# WiFi_module.net
KiCad netlist of a schematic drawn in Altium Designer
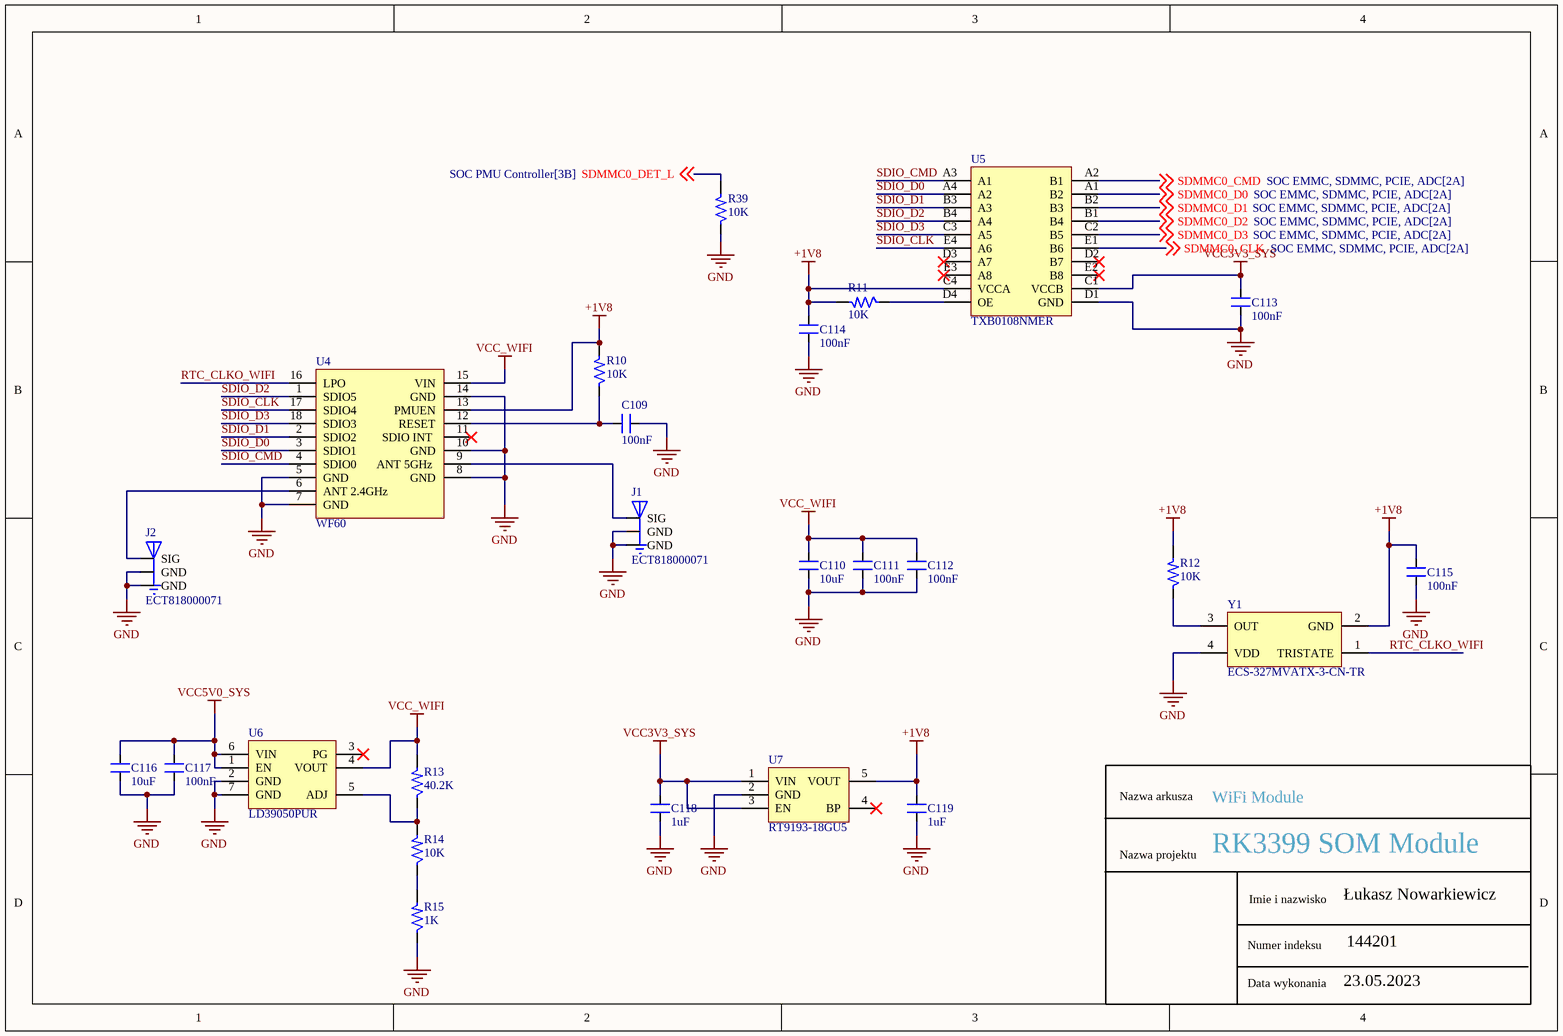
[diagram p0: WiFi module.SchDoc]

(export (version "E")
  (design (tool "Eeschema 10.0.6"))
  (components
    (comp (ref "C109")
      (value "100nF")
      (footprint "CAP_0402")
      (description "0.1µF ±10% 10V Ceramic Capacitor X7R 0402 (1005 Metric)")
      (fields
        (field (name "MANUFACTURER") "Yageo")
        (field (name "MANUFACTURER PART NUMBER") "CC0402KRX7R6BB104")
      )
      (libsource (lib "EsteemPCB_SOM_Course_intlib") (part "CAP_100nF-10V-10%-0402"))
    )
    (comp (ref "C110")
      (value "10uF")
      (footprint "CAP_0603")
      (description "10µF ±10% 10V Ceramic Capacitor X5R 0603 (1608 Metric)")
      (fields
        (field (name "MANUFACTURER PART NUMBER") "GRM188R61A106KE69J")
        (field (name "MANUFACTURER") "Murata Electronics")
      )
      (libsource (lib "EsteemPCB_SOM_Course_intlib") (part "CAP_10uF-10V-10%-0603"))
    )
    (comp (ref "C111")
      (value "100nF")
      (footprint "CAP_0402")
      (description "0.1µF ±10% 10V Ceramic Capacitor X7R 0402 (1005 Metric)")
      (fields
        (field (name "MANUFACTURER") "Yageo")
        (field (name "MANUFACTURER PART NUMBER") "CC0402KRX7R6BB104")
      )
      (libsource (lib "EsteemPCB_SOM_Course_intlib") (part "CAP_100nF-10V-10%-0402"))
    )
    (comp (ref "C112")
      (value "100nF")
      (footprint "CAP_0402")
      (description "0.1µF ±10% 10V Ceramic Capacitor X7R 0402 (1005 Metric)")
      (fields
        (field (name "MANUFACTURER") "Yageo")
        (field (name "MANUFACTURER PART NUMBER") "CC0402KRX7R6BB104")
      )
      (libsource (lib "EsteemPCB_SOM_Course_intlib") (part "CAP_100nF-10V-10%-0402"))
    )
    (comp (ref "C113")
      (value "100nF")
      (footprint "CAP_0402")
      (description "0.1µF ±10% 10V Ceramic Capacitor X7R 0402 (1005 Metric)")
      (fields
        (field (name "MANUFACTURER") "Yageo")
        (field (name "MANUFACTURER PART NUMBER") "CC0402KRX7R6BB104")
      )
      (libsource (lib "EsteemPCB_SOM_Course_intlib") (part "CAP_100nF-10V-10%-0402"))
    )
    (comp (ref "C114")
      (value "100nF")
      (footprint "CAP_0402")
      (description "0.1µF ±10% 10V Ceramic Capacitor X7R 0402 (1005 Metric)")
      (fields
        (field (name "MANUFACTURER") "Yageo")
        (field (name "MANUFACTURER PART NUMBER") "CC0402KRX7R6BB104")
      )
      (libsource (lib "EsteemPCB_SOM_Course_intlib") (part "CAP_100nF-10V-10%-0402"))
    )
    (comp (ref "C115")
      (value "100nF")
      (footprint "CAP_0402")
      (description "0.1µF ±10% 10V Ceramic Capacitor X7R 0402 (1005 Metric)")
      (fields
        (field (name "MANUFACTURER") "Yageo")
        (field (name "MANUFACTURER PART NUMBER") "CC0402KRX7R6BB104")
      )
      (libsource (lib "EsteemPCB_SOM_Course_intlib") (part "CAP_100nF-10V-10%-0402"))
    )
    (comp (ref "C116")
      (value "10uF")
      (footprint "CAP_0603")
      (description "10µF ±10% 10V Ceramic Capacitor X5R 0603 (1608 Metric)")
      (fields
        (field (name "MANUFACTURER PART NUMBER") "GRM188R61A106KE69J")
        (field (name "MANUFACTURER") "Murata Electronics")
      )
      (libsource (lib "EsteemPCB_SOM_Course_intlib") (part "CAP_10uF-10V-10%-0603"))
    )
    (comp (ref "C117")
      (value "100nF")
      (footprint "CAP_0402")
      (description "0.1µF ±10% 10V Ceramic Capacitor X7R 0402 (1005 Metric)")
      (fields
        (field (name "MANUFACTURER") "Yageo")
        (field (name "MANUFACTURER PART NUMBER") "CC0402KRX7R6BB104")
      )
      (libsource (lib "EsteemPCB_SOM_Course_intlib") (part "CAP_100nF-10V-10%-0402"))
    )
    (comp (ref "C118")
      (value "1uF")
      (footprint "CAP_0402")
      (description "1µF ±10% 10V Ceramic Capacitor X6S 0402 (1005 Metric)")
      (fields
        (field (name "MANUFACTURER") "Murata Electronics")
        (field (name "MANUFACTURER PART NUMBER") "GRT155C81A105KE01D")
      )
      (libsource (lib "EsteemPCB_SOM_Course_intlib") (part "CAP_1uF-10V-10%-0402"))
    )
    (comp (ref "C119")
      (value "1uF")
      (footprint "CAP_0402")
      (description "1µF ±10% 10V Ceramic Capacitor X6S 0402 (1005 Metric)")
      (fields
        (field (name "MANUFACTURER") "Murata Electronics")
        (field (name "MANUFACTURER PART NUMBER") "GRT155C81A105KE01D")
      )
      (libsource (lib "EsteemPCB_SOM_Course_intlib") (part "CAP_1uF-10V-10%-0402"))
    )
    (comp (ref "J1")
      (value "ECT818000071")
      (footprint "CON3_UFL_116_SMD_ST")
      (description "SMD RF Connectors/Coaxial Connectors RoHS")
      (fields (field (name "MANUFACTURER") "ECT"))
      (libsource (lib "EsteemPCB_SOM_Course_intlib") (part "CON-PLG_3X1-ECT818000071-ST-SMD"))
    )
    (comp (ref "J2")
      (value "ECT818000071")
      (footprint "CON3_UFL_116_SMD_ST")
      (description "SMD RF Connectors/Coaxial Connectors RoHS")
      (fields (field (name "MANUFACTURER") "ECT"))
      (libsource (lib "EsteemPCB_SOM_Course_intlib") (part "CON-PLG_3X1-ECT818000071-ST-SMD"))
    )
    (comp (ref "R10")
      (value "10K")
      (footprint "RES_0201")
      (description "10 kOhms ±1% 0.05W, 1/20W Chip Resistor 0201 (0603 Metric) Thick Film")
      (fields
        (field (name "MANUFACTURER") "Stackpole Electronics Inc")
        (field (name "MANUFACTURER PART NUMBER") "RMCF0201FT10K0")
      )
      (libsource (lib "EsteemPCB_SOM_Course_intlib") (part "RES_10K-0.05W-1%-0201"))
    )
    (comp (ref "R11")
      (value "10K")
      (footprint "RES_0201")
      (description "10 kOhms ±1% 0.05W, 1/20W Chip Resistor 0201 (0603 Metric) Thick Film")
      (fields
        (field (name "MANUFACTURER") "Stackpole Electronics Inc")
        (field (name "MANUFACTURER PART NUMBER") "RMCF0201FT10K0")
      )
      (libsource (lib "EsteemPCB_SOM_Course_intlib") (part "RES_10K-0.05W-1%-0201"))
    )
    (comp (ref "R12")
      (value "10K")
      (footprint "RES_0201")
      (description "10 kOhms ±1% 0.05W, 1/20W Chip Resistor 0201 (0603 Metric) Thick Film")
      (fields
        (field (name "MANUFACTURER") "Stackpole Electronics Inc")
        (field (name "MANUFACTURER PART NUMBER") "RMCF0201FT10K0")
      )
      (libsource (lib "EsteemPCB_SOM_Course_intlib") (part "RES_10K-0.05W-1%-0201"))
    )
    (comp (ref "R13")
      (value "40.2K")
      (footprint "RES_0201")
      (fields
        (field (name "MANUFACTURER") "Yageo")
        (field (name "MANUFACTURER PART NUMBER") "AC0201FR-0740K2L")
      )
      (libsource (lib "EsteemPCB_SOM_Course_intlib") (part "RES_40.2K-0.05W-1%-0201"))
    )
    (comp (ref "R14")
      (value "10K")
      (footprint "RES_0201")
      (description "10 kOhms ±1% 0.05W, 1/20W Chip Resistor 0201 (0603 Metric) Thick Film")
      (fields
        (field (name "MANUFACTURER") "Stackpole Electronics Inc")
        (field (name "MANUFACTURER PART NUMBER") "RMCF0201FT10K0")
      )
      (libsource (lib "EsteemPCB_SOM_Course_intlib") (part "RES_10K-0.05W-1%-0201"))
    )
    (comp (ref "R15")
      (value "1K")
      (footprint "RES_0201")
      (description "1 kOhms ±1% 0.05W, 1/20W Chip Resistor 0201 (0603 Metric) Thick Film")
      (fields
        (field (name "MANUFACTURER") "Yageo")
        (field (name "MANUFACTURER PART NUMBER") "RC0201FR-071KL")
      )
      (libsource (lib "EsteemPCB_SOM_Course_intlib") (part "RES_1K-0.05W-1%-0201"))
    )
    (comp (ref "R39")
      (value "10K")
      (footprint "RES_0402")
      (description "10 kOhms ±1% 0.1W, 1/10W Chip Resistor 0402 (1005 Metric) Anti-Sulfur Thin Film")
      (fields
        (field (name "MANUFACTURER") "Vishay Beyschlag/Draloric/BC Components")
        (field (name "MANUFACTURER PART NUMBER") "MCS04020C1002FE000")
      )
      (libsource (lib "RK3399 _Module_Intlib") (part "RES_10K-0.1W-1%-0402"))
    )
    (comp (ref "U4")
      (value "WF60")
      (footprint "MOD_WF60")
      (description "Amp’ed RF Tech presents the WF60 WiFi dual\r\nband module: 802.11abgn.")
      (fields (field (name "MANUFACTURER") "Amp’ed"))
      (libsource (lib "EsteemPCB_SOM_Course_intlib") (part "MOD_WF60-SMD"))
    )
    (comp (ref "U5")
      (value "TXB0108NMER")
      (footprint "NFBGA_31.4_125.9X102.36")
      (fields (field (name "MANUFACTURER") "Texas Instruments"))
      (libsource (lib "EsteemPCB_SOM_Course_intlib") (part "IC_TXB0108NMER"))
    )
    (comp (ref "U6")
      (value "LD39050PUR")
      (footprint "DFN-6_37.4_165_33X15_SMD")
      (description "Adjustable 5.5V 0.8V 500mA DFN-6 Linear Voltage Regulators RoHS")
      (fields (field (name "MANUFACTURER") "STMicroelectronics"))
      (libsource (lib "EsteemPCB_SOM_Course_intlib") (part "REG_5.5V-0~5.1V-0.5A-2.55W-DFN-6"))
    )
    (comp (ref "U7")
      (value "RT9193-18GU5")
      (footprint "SC70-5")
      (description "Linear Voltage Regulator IC 1 Output 300mA SC-70-5")
      (fields (field (name "MANUFACTURER") "Richtek USA Inc."))
      (libsource (lib "EsteemPCB_SOM_Course_intlib") (part "REG_1.8V-300mA-5.5V-SC70-5"))
    )
    (comp (ref "Y1")
      (value "ECS-327MVATX-3-CN-TR")
      (footprint "XTAL_57_35X31_SMD")
      (description "32.768kHz XO (Standard) CMOS Oscillator 1.6V ~ 3.6V Enable/Disable 4-SMD, No Lead")
      (fields (field (name "MANUFACTURER") "ECS INC"))
      (libsource (lib "EsteemPCB_SOM_Course_intlib") (part "XTAL_ECS-327MVATX-2-CN-TR"))
    )
  )
  (nets
    (net (code "1") (name "+1V8") (class "Default")
      (node (ref "C114") (pin "2") (pinfunction "2_2") (pintype "passive"))
      (node (ref "C115") (pin "2") (pinfunction "2_2") (pintype "passive"))
      (node (ref "C119") (pin "2") (pinfunction "2_2") (pintype "passive"))
      (node (ref "R10") (pin "2") (pinfunction "2_2") (pintype "passive"))
      (node (ref "R11") (pin "2") (pinfunction "2_2") (pintype "passive"))
      (node (ref "R12") (pin "2") (pinfunction "2_2") (pintype "passive"))
      (node (ref "U4") (pin "13") (pinfunction "PMUEN_13") (pintype "passive"))
      (node (ref "U5") (pin "C4") (pinfunction "VCCA_C4") (pintype "passive"))
      (node (ref "U7") (pin "5") (pinfunction "VOUT_5") (pintype "passive"))
      (node (ref "Y1") (pin "2") (pinfunction "GND_2") (pintype "passive"))
    )
    (net (code "2") (name "/RTC_CLKO_WIFI") (class "Default")
      (node (ref "U4") (pin "16") (pinfunction "LPO_16") (pintype "passive"))
      (node (ref "Y1") (pin "1") (pinfunction "TRISTATE_1") (pintype "passive"))
    )
    (net (code "3") (name "/SDIO_CLK") (class "Default")
      (node (ref "U4") (pin "17") (pinfunction "SDIO4_17") (pintype "passive"))
      (node (ref "U5") (pin "E4") (pinfunction "A6_E4") (pintype "passive"))
    )
    (net (code "4") (name "/SDIO_CMD") (class "Default")
      (node (ref "U4") (pin "4") (pinfunction "SDIO0_4") (pintype "passive"))
      (node (ref "U5") (pin "A3") (pinfunction "A1_A3") (pintype "passive"))
    )
    (net (code "5") (name "/SDIO_D0") (class "Default")
      (node (ref "U4") (pin "3") (pinfunction "SDIO1_3") (pintype "passive"))
      (node (ref "U5") (pin "A4") (pinfunction "A2_A4") (pintype "passive"))
    )
    (net (code "6") (name "/SDIO_D1") (class "Default")
      (node (ref "U4") (pin "2") (pinfunction "SDIO2_2") (pintype "passive"))
      (node (ref "U5") (pin "B3") (pinfunction "A3_B3") (pintype "passive"))
    )
    (net (code "7") (name "/SDIO_D2") (class "Default")
      (node (ref "U4") (pin "1") (pinfunction "SDIO5_1") (pintype "passive"))
      (node (ref "U5") (pin "B4") (pinfunction "A4_B4") (pintype "passive"))
    )
    (net (code "8") (name "/SDIO_D3") (class "Default")
      (node (ref "U4") (pin "18") (pinfunction "SDIO3_18") (pintype "passive"))
      (node (ref "U5") (pin "C3") (pinfunction "A5_C3") (pintype "passive"))
    )
    (net (code "9") (name "GND") (class "Default")
      (node (ref "C109") (pin "2") (pinfunction "2_2") (pintype "passive"))
      (node (ref "C110") (pin "1") (pinfunction "1_1") (pintype "passive"))
      (node (ref "C111") (pin "1") (pinfunction "1_1") (pintype "passive"))
      (node (ref "C112") (pin "2") (pinfunction "2_2") (pintype "passive"))
      (node (ref "C113") (pin "1") (pinfunction "1_1") (pintype "passive"))
      (node (ref "C114") (pin "1") (pinfunction "1_1") (pintype "passive"))
      (node (ref "C115") (pin "1") (pinfunction "1_1") (pintype "passive"))
      (node (ref "C116") (pin "1") (pinfunction "1_1") (pintype "passive"))
      (node (ref "C117") (pin "1") (pinfunction "1_1") (pintype "passive"))
      (node (ref "C118") (pin "1") (pinfunction "1_1") (pintype "passive"))
      (node (ref "C119") (pin "1") (pinfunction "1_1") (pintype "passive"))
      (node (ref "J1") (pin "1") (pinfunction "GND_1") (pintype "passive"))
      (node (ref "J1") (pin "3") (pinfunction "GND_3") (pintype "passive"))
      (node (ref "J2") (pin "1") (pinfunction "GND_1") (pintype "passive"))
      (node (ref "J2") (pin "3") (pinfunction "GND_3") (pintype "passive"))
      (node (ref "R15") (pin "1") (pinfunction "1_1") (pintype "passive"))
      (node (ref "R39") (pin "1") (pinfunction "1_1") (pintype "passive"))
      (node (ref "U4") (pin "10") (pinfunction "GND_10") (pintype "passive"))
      (node (ref "U4") (pin "14") (pinfunction "GND_14") (pintype "passive"))
      (node (ref "U4") (pin "5") (pinfunction "GND_5") (pintype "passive"))
      (node (ref "U4") (pin "7") (pinfunction "GND_7") (pintype "passive"))
      (node (ref "U4") (pin "8") (pinfunction "GND_8") (pintype "passive"))
      (node (ref "U5") (pin "D1") (pinfunction "GND_D1") (pintype "passive"))
      (node (ref "U6") (pin "2") (pinfunction "GND_2") (pintype "passive"))
      (node (ref "U6") (pin "7") (pinfunction "GND_7") (pintype "passive"))
      (node (ref "U7") (pin "2") (pinfunction "GND_2") (pintype "passive"))
      (node (ref "Y1") (pin "4") (pinfunction "VDD_4") (pintype "passive"))
    )
    (net (code "10") (name "Net-(J1-SIG)") (class "Default")
      (node (ref "J1") (pin "2") (pinfunction "SIG_2") (pintype "passive"))
      (node (ref "U4") (pin "9") (pinfunction "ANT_5GHz_9") (pintype "passive"))
    )
    (net (code "11") (name "Net-(J2-SIG)") (class "Default")
      (node (ref "J2") (pin "2") (pinfunction "SIG_2") (pintype "passive"))
      (node (ref "U4") (pin "6") (pinfunction "ANT_2.4GHz_6") (pintype "passive"))
    )
    (net (code "12") (name "Net-(R14-Pad1)") (class "Default")
      (node (ref "R14") (pin "1") (pinfunction "1_1") (pintype "passive"))
      (node (ref "R15") (pin "2") (pinfunction "2_2") (pintype "passive"))
    )
    (net (code "13") (name "Net-(U4-RESET)") (class "Default")
      (node (ref "C109") (pin "1") (pinfunction "1_1") (pintype "passive"))
      (node (ref "R10") (pin "1") (pinfunction "1_1") (pintype "passive"))
      (node (ref "U4") (pin "12") (pinfunction "RESET_12") (pintype "passive"))
    )
    (net (code "14") (name "Net-(U5-OE)") (class "Default")
      (node (ref "R11") (pin "1") (pinfunction "1_1") (pintype "passive"))
      (node (ref "U5") (pin "D4") (pinfunction "OE_D4") (pintype "passive"))
    )
    (net (code "15") (name "Net-(U6-ADJ)") (class "Default")
      (node (ref "R13") (pin "1") (pinfunction "1_1") (pintype "passive"))
      (node (ref "R14") (pin "2") (pinfunction "2_2") (pintype "passive"))
      (node (ref "U6") (pin "5") (pinfunction "ADJ_5") (pintype "passive"))
    )
    (net (code "16") (name "Net-(Y1-OUT)") (class "Default")
      (node (ref "R12") (pin "1") (pinfunction "1_1") (pintype "passive"))
      (node (ref "Y1") (pin "3") (pinfunction "OUT_3") (pintype "passive"))
    )
    (net (code "17") (name "SDMMC0_CLK") (class "Default")
      (node (ref "U5") (pin "E1") (pinfunction "B6_E1") (pintype "passive"))
    )
    (net (code "18") (name "SDMMC0_CMD") (class "Default")
      (node (ref "U5") (pin "A2") (pinfunction "B1_A2") (pintype "passive"))
    )
    (net (code "19") (name "SDMMC0_D0") (class "Default")
      (node (ref "U5") (pin "A1") (pinfunction "B2_A1") (pintype "passive"))
    )
    (net (code "20") (name "SDMMC0_D1") (class "Default")
      (node (ref "U5") (pin "B2") (pinfunction "B3_B2") (pintype "passive"))
    )
    (net (code "21") (name "SDMMC0_D2") (class "Default")
      (node (ref "U5") (pin "B1") (pinfunction "B4_B1") (pintype "passive"))
    )
    (net (code "22") (name "SDMMC0_D3") (class "Default")
      (node (ref "U5") (pin "C2") (pinfunction "B5_C2") (pintype "passive"))
    )
    (net (code "23") (name "SDMMC0_DET_L") (class "Default")
      (node (ref "R39") (pin "2") (pinfunction "2_2") (pintype "passive"))
    )
    (net (code "24") (name "VCC3V3_SYS") (class "Default")
      (node (ref "C113") (pin "2") (pinfunction "2_2") (pintype "passive"))
      (node (ref "C118") (pin "2") (pinfunction "2_2") (pintype "passive"))
      (node (ref "U5") (pin "C1") (pinfunction "VCCB_C1") (pintype "passive"))
      (node (ref "U7") (pin "1") (pinfunction "VIN_1") (pintype "passive"))
      (node (ref "U7") (pin "3") (pinfunction "EN_3") (pintype "passive"))
    )
    (net (code "25") (name "VCC5V0_SYS") (class "Default")
      (node (ref "C116") (pin "2") (pinfunction "2_2") (pintype "passive"))
      (node (ref "C117") (pin "2") (pinfunction "2_2") (pintype "passive"))
      (node (ref "U6") (pin "1") (pinfunction "EN_1") (pintype "passive"))
      (node (ref "U6") (pin "6") (pinfunction "VIN_6") (pintype "passive"))
    )
    (net (code "26") (name "VCC_WIFI") (class "Default")
      (node (ref "C110") (pin "2") (pinfunction "2_2") (pintype "passive"))
      (node (ref "C111") (pin "2") (pinfunction "2_2") (pintype "passive"))
      (node (ref "C112") (pin "1") (pinfunction "1_1") (pintype "passive"))
      (node (ref "R13") (pin "2") (pinfunction "2_2") (pintype "passive"))
      (node (ref "U4") (pin "15") (pinfunction "VIN_15") (pintype "passive"))
      (node (ref "U6") (pin "4") (pinfunction "VOUT_4") (pintype "passive"))
    )
    (net (code "27") (name "unconnected-(U4-SDIO_INT-Pad11)") (class "Default")
      (node (ref "U4") (pin "11") (pinfunction "SDIO_INT_11") (pintype "passive+no_connect"))
    )
    (net (code "28") (name "unconnected-(U5-A7-PadD3)") (class "Default")
      (node (ref "U5") (pin "D3") (pinfunction "A7_D3") (pintype "passive+no_connect"))
    )
    (net (code "29") (name "unconnected-(U5-A8-PadE3)") (class "Default")
      (node (ref "U5") (pin "E3") (pinfunction "A8_E3") (pintype "passive+no_connect"))
    )
    (net (code "30") (name "unconnected-(U5-B7-PadD2)") (class "Default")
      (node (ref "U5") (pin "D2") (pinfunction "B7_D2") (pintype "passive+no_connect"))
    )
    (net (code "31") (name "unconnected-(U5-B8-PadE2)") (class "Default")
      (node (ref "U5") (pin "E2") (pinfunction "B8_E2") (pintype "passive+no_connect"))
    )
    (net (code "32") (name "unconnected-(U6-PG-Pad3)") (class "Default")
      (node (ref "U6") (pin "3") (pinfunction "PG_3") (pintype "passive+no_connect"))
    )
    (net (code "33") (name "unconnected-(U7-BP-Pad4)") (class "Default")
      (node (ref "U7") (pin "4") (pinfunction "BP_4") (pintype "passive+no_connect"))
    )
  )
)
